# Sensor_LED_board.net
KiCad netlist of a schematic drawn in EAGLE
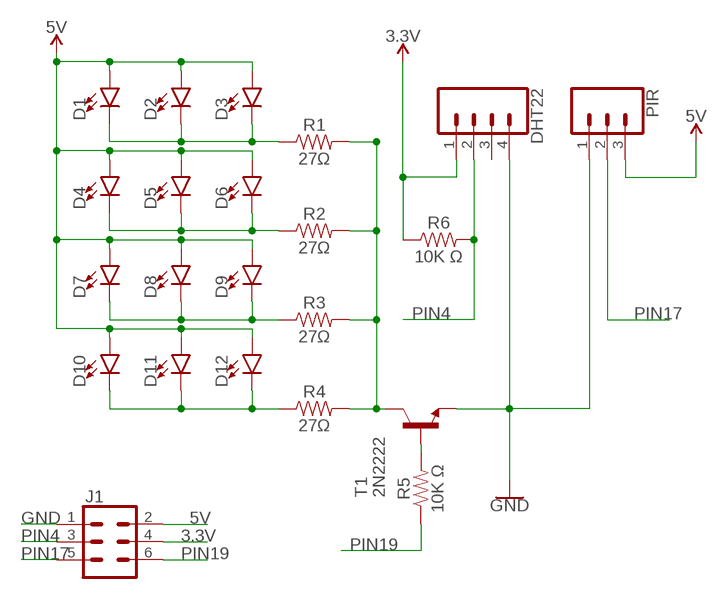
[diagram p0: schematic, sheet 1]

(export (version "E")
  (design (tool "Eeschema 10.0.6"))
  (components
    (comp (ref "D1")
      (value "LED5MM")
      (footprint "eagle-import:LED_5MM")
      (libsource (lib "eagle-import") (part "LED5MM"))
    )
    (comp (ref "D2")
      (value "LED5MM")
      (footprint "eagle-import:LED_5MM")
      (libsource (lib "eagle-import") (part "LED5MM"))
    )
    (comp (ref "D3")
      (value "LED5MM")
      (footprint "eagle-import:LED_5MM")
      (libsource (lib "eagle-import") (part "LED5MM"))
    )
    (comp (ref "D4")
      (value "LED5MM")
      (footprint "eagle-import:LED_5MM")
      (libsource (lib "eagle-import") (part "LED5MM"))
    )
    (comp (ref "D5")
      (value "LED5MM")
      (footprint "eagle-import:LED_5MM")
      (libsource (lib "eagle-import") (part "LED5MM"))
    )
    (comp (ref "D6")
      (value "LED5MM")
      (footprint "eagle-import:LED_5MM")
      (libsource (lib "eagle-import") (part "LED5MM"))
    )
    (comp (ref "D7")
      (value "LED5MM")
      (footprint "eagle-import:LED_5MM")
      (libsource (lib "eagle-import") (part "LED5MM"))
    )
    (comp (ref "D8")
      (value "LED5MM")
      (footprint "eagle-import:LED_5MM")
      (libsource (lib "eagle-import") (part "LED5MM"))
    )
    (comp (ref "D9")
      (value "LED5MM")
      (footprint "eagle-import:LED_5MM")
      (libsource (lib "eagle-import") (part "LED5MM"))
    )
    (comp (ref "D10")
      (value "LED5MM")
      (footprint "eagle-import:LED_5MM")
      (libsource (lib "eagle-import") (part "LED5MM"))
    )
    (comp (ref "D11")
      (value "LED5MM")
      (footprint "eagle-import:LED_5MM")
      (libsource (lib "eagle-import") (part "LED5MM"))
    )
    (comp (ref "D12")
      (value "LED5MM")
      (footprint "eagle-import:LED_5MM")
      (libsource (lib "eagle-import") (part "LED5MM"))
    )
    (comp (ref "DHT22")
      (value "CONN_04LONGPADS")
      (footprint "eagle-import:1X04_LONGPADS")
      (libsource (lib "eagle-import") (part "CONN_04LONGPADS"))
    )
    (comp (ref "J1")
      (value "CONN_03X2SHROUD")
      (footprint "eagle-import:2X3-SHROUDED")
      (libsource (lib "eagle-import") (part "CONN_03X2SHROUD"))
    )
    (comp (ref "PIR")
      (value "CONN_03LONGPADS")
      (footprint "eagle-import:1X03_LONGPADS")
      (libsource (lib "eagle-import") (part "CONN_03LONGPADS"))
    )
    (comp (ref "R1")
      (value "27Ω")
      (footprint "eagle-import:AXIAL-0.3-KIT")
      (libsource (lib "eagle-import") (part "10OHM-HORIZ_KIT-1/4W-1%"))
    )
    (comp (ref "R2")
      (value "27Ω")
      (footprint "eagle-import:AXIAL-0.3-KIT")
      (libsource (lib "eagle-import") (part "10OHM-HORIZ_KIT-1/4W-1%"))
    )
    (comp (ref "R3")
      (value "27Ω")
      (footprint "eagle-import:AXIAL-0.3-KIT")
      (libsource (lib "eagle-import") (part "10OHM-HORIZ_KIT-1/4W-1%"))
    )
    (comp (ref "R4")
      (value "27Ω")
      (footprint "eagle-import:AXIAL-0.3-KIT")
      (libsource (lib "eagle-import") (part "10OHM-HORIZ_KIT-1/4W-1%"))
    )
    (comp (ref "R5")
      (value "10K Ω")
      (footprint "eagle-import:AXIAL-0.3-KIT")
      (libsource (lib "eagle-import") (part "10OHM-HORIZ_KIT-1/4W-1%"))
    )
    (comp (ref "R6")
      (value "10K Ω")
      (footprint "eagle-import:AXIAL-0.3-KIT")
      (libsource (lib "eagle-import") (part "10OHM-HORIZ_KIT-1/4W-1%"))
    )
    (comp (ref "T1")
      (value "2N2222")
      (footprint "eagle-import:TO92-EBC-OVAL")
      (libsource (lib "eagle-import") (part "2N2222"))
    )
  )
  (nets
    (net (code "1") (name "/PIN4") (class "Default")
      (node (ref "DHT22") (pin "2") (pinfunction "2_2") (pintype "passive"))
      (node (ref "J1") (pin "3") (pinfunction "3_3") (pintype "bidirectional"))
      (node (ref "R6") (pin "P$2") (pinfunction "2_P$2") (pintype "passive"))
    )
    (net (code "2") (name "/PIN17") (class "Default")
      (node (ref "J1") (pin "5") (pinfunction "5_5") (pintype "bidirectional"))
      (node (ref "PIR") (pin "2") (pinfunction "2_2") (pintype "passive"))
    )
    (net (code "3") (name "/PIN19") (class "Default")
      (node (ref "J1") (pin "6") (pinfunction "6_6") (pintype "bidirectional"))
      (node (ref "R5") (pin "P$1") (pinfunction "1_P$1") (pintype "passive"))
    )
    (net (code "4") (name "3.3V") (class "Default")
      (node (ref "DHT22") (pin "1") (pinfunction "1_1") (pintype "passive"))
      (node (ref "J1") (pin "4") (pinfunction "4_4") (pintype "bidirectional"))
      (node (ref "R6") (pin "P$1") (pinfunction "1_P$1") (pintype "passive"))
    )
    (net (code "5") (name "5V") (class "Default")
      (node (ref "D1") (pin "A") (pinfunction "A_A") (pintype "passive"))
      (node (ref "D10") (pin "A") (pinfunction "A_A") (pintype "passive"))
      (node (ref "D11") (pin "A") (pinfunction "A_A") (pintype "passive"))
      (node (ref "D12") (pin "A") (pinfunction "A_A") (pintype "passive"))
      (node (ref "D2") (pin "A") (pinfunction "A_A") (pintype "passive"))
      (node (ref "D3") (pin "A") (pinfunction "A_A") (pintype "passive"))
      (node (ref "D4") (pin "A") (pinfunction "A_A") (pintype "passive"))
      (node (ref "D5") (pin "A") (pinfunction "A_A") (pintype "passive"))
      (node (ref "D6") (pin "A") (pinfunction "A_A") (pintype "passive"))
      (node (ref "D7") (pin "A") (pinfunction "A_A") (pintype "passive"))
      (node (ref "D8") (pin "A") (pinfunction "A_A") (pintype "passive"))
      (node (ref "D9") (pin "A") (pinfunction "A_A") (pintype "passive"))
      (node (ref "J1") (pin "2") (pinfunction "2_2") (pintype "bidirectional"))
      (node (ref "PIR") (pin "3") (pinfunction "3_3") (pintype "passive"))
    )
    (net (code "6") (name "GND") (class "Default")
      (node (ref "DHT22") (pin "4") (pinfunction "4_4") (pintype "passive"))
      (node (ref "J1") (pin "1") (pinfunction "1_1") (pintype "bidirectional"))
      (node (ref "PIR") (pin "1") (pinfunction "1_1") (pintype "passive"))
      (node (ref "T1") (pin "E") (pinfunction "E_E") (pintype "passive"))
    )
    (net (code "7") (name "Net-(D1-C)") (class "Default")
      (node (ref "D1") (pin "K") (pinfunction "C_K") (pintype "passive"))
      (node (ref "D2") (pin "K") (pinfunction "C_K") (pintype "passive"))
      (node (ref "D3") (pin "K") (pinfunction "C_K") (pintype "passive"))
      (node (ref "R1") (pin "P$1") (pinfunction "1_P$1") (pintype "passive"))
    )
    (net (code "8") (name "Net-(D4-C)") (class "Default")
      (node (ref "D4") (pin "K") (pinfunction "C_K") (pintype "passive"))
      (node (ref "D5") (pin "K") (pinfunction "C_K") (pintype "passive"))
      (node (ref "D6") (pin "K") (pinfunction "C_K") (pintype "passive"))
      (node (ref "R2") (pin "P$1") (pinfunction "1_P$1") (pintype "passive"))
    )
    (net (code "9") (name "Net-(D7-C)") (class "Default")
      (node (ref "D7") (pin "K") (pinfunction "C_K") (pintype "passive"))
      (node (ref "D8") (pin "K") (pinfunction "C_K") (pintype "passive"))
      (node (ref "D9") (pin "K") (pinfunction "C_K") (pintype "passive"))
      (node (ref "R3") (pin "P$1") (pinfunction "1_P$1") (pintype "passive"))
    )
    (net (code "10") (name "Net-(D10-C)") (class "Default")
      (node (ref "D10") (pin "K") (pinfunction "C_K") (pintype "passive"))
      (node (ref "D11") (pin "K") (pinfunction "C_K") (pintype "passive"))
      (node (ref "D12") (pin "K") (pinfunction "C_K") (pintype "passive"))
      (node (ref "R4") (pin "P$1") (pinfunction "1_P$1") (pintype "passive"))
    )
    (net (code "11") (name "Net-(R1-2)") (class "Default")
      (node (ref "R1") (pin "P$2") (pinfunction "2_P$2") (pintype "passive"))
      (node (ref "R2") (pin "P$2") (pinfunction "2_P$2") (pintype "passive"))
      (node (ref "R3") (pin "P$2") (pinfunction "2_P$2") (pintype "passive"))
      (node (ref "R4") (pin "P$2") (pinfunction "2_P$2") (pintype "passive"))
      (node (ref "T1") (pin "C") (pinfunction "C_C") (pintype "passive"))
    )
    (net (code "12") (name "Net-(R5-2)") (class "Default")
      (node (ref "R5") (pin "P$2") (pinfunction "2_P$2") (pintype "passive"))
      (node (ref "T1") (pin "B") (pinfunction "B_B") (pintype "passive"))
    )
    (net (code "13") (name "unconnected-(DHT22-Pad3)") (class "Default")
      (node (ref "DHT22") (pin "3") (pinfunction "3_3") (pintype "passive"))
    )
  )
)
